# schematic-both.net
KiCad netlist of a schematic drawn in EAGLE
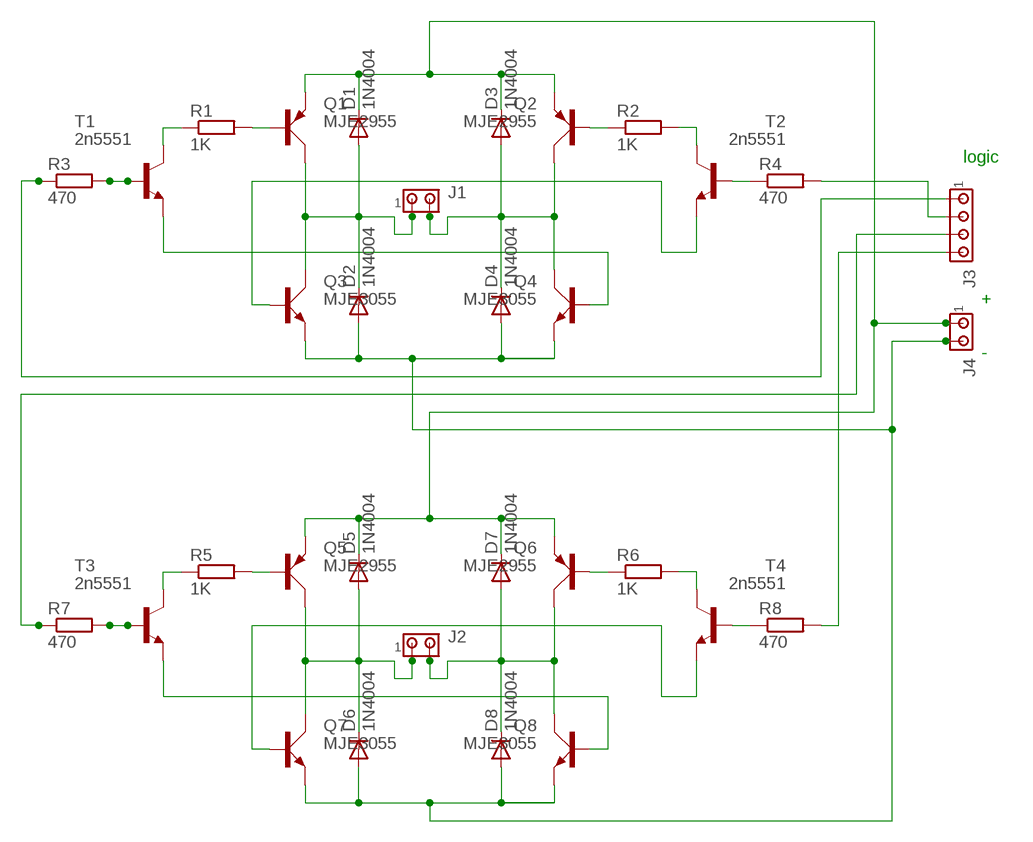
[diagram p0: schematic, sheet 1]

(export (version "E")
  (design (tool "Eeschema 10.0.6"))
  (components
    (comp (ref "D1")
      (value "1N4004")
      (footprint "eagle-import:DO41-10")
      (libsource (lib "eagle-import") (part "1N4004"))
    )
    (comp (ref "D2")
      (value "1N4004")
      (footprint "eagle-import:DO41-10")
      (libsource (lib "eagle-import") (part "1N4004"))
    )
    (comp (ref "D3")
      (value "1N4004")
      (footprint "eagle-import:DO41-10")
      (libsource (lib "eagle-import") (part "1N4004"))
    )
    (comp (ref "D4")
      (value "1N4004")
      (footprint "eagle-import:DO41-10")
      (libsource (lib "eagle-import") (part "1N4004"))
    )
    (comp (ref "D5")
      (value "1N4004")
      (footprint "eagle-import:DO41-10")
      (libsource (lib "eagle-import") (part "1N4004"))
    )
    (comp (ref "D6")
      (value "1N4004")
      (footprint "eagle-import:DO41-10")
      (libsource (lib "eagle-import") (part "1N4004"))
    )
    (comp (ref "D7")
      (value "1N4004")
      (footprint "eagle-import:DO41-10")
      (libsource (lib "eagle-import") (part "1N4004"))
    )
    (comp (ref "D8")
      (value "1N4004")
      (footprint "eagle-import:DO41-10")
      (libsource (lib "eagle-import") (part "1N4004"))
    )
    (comp (ref "J1")
      (value "MTA02-156")
      (footprint "eagle-import:1X2MTA")
      (libsource (lib "eagle-import") (part "MTA02-156"))
    )
    (comp (ref "J2")
      (value "MTA02-156")
      (footprint "eagle-import:1X2MTA")
      (libsource (lib "eagle-import") (part "MTA02-156"))
    )
    (comp (ref "J3")
      (value "MTA04-100")
      (footprint "eagle-import:10X04MTA")
      (libsource (lib "eagle-import") (part "MTA04-100"))
    )
    (comp (ref "J4")
      (value "MTA02-156")
      (footprint "eagle-import:1X2MTA")
      (libsource (lib "eagle-import") (part "MTA02-156"))
    )
    (comp (ref "Q1")
      (value "MJE2955")
      (footprint "eagle-import:TO220AV")
      (libsource (lib "eagle-import") (part "MJE2955"))
    )
    (comp (ref "Q2")
      (value "MJE2955")
      (footprint "eagle-import:TO220AV")
      (libsource (lib "eagle-import") (part "MJE2955"))
    )
    (comp (ref "Q3")
      (value "MJE3055")
      (footprint "eagle-import:TO220AV")
      (libsource (lib "eagle-import") (part "MJE3055"))
    )
    (comp (ref "Q4")
      (value "MJE3055")
      (footprint "eagle-import:TO220AV")
      (libsource (lib "eagle-import") (part "MJE3055"))
    )
    (comp (ref "Q5")
      (value "MJE2955")
      (footprint "eagle-import:TO220AV")
      (libsource (lib "eagle-import") (part "MJE2955"))
    )
    (comp (ref "Q6")
      (value "MJE2955")
      (footprint "eagle-import:TO220AV")
      (libsource (lib "eagle-import") (part "MJE2955"))
    )
    (comp (ref "Q7")
      (value "MJE3055")
      (footprint "eagle-import:TO220AV")
      (libsource (lib "eagle-import") (part "MJE3055"))
    )
    (comp (ref "Q8")
      (value "MJE3055")
      (footprint "eagle-import:TO220AV")
      (libsource (lib "eagle-import") (part "MJE3055"))
    )
    (comp (ref "R1")
      (value "1K")
      (footprint "eagle-import:0204_7")
      (libsource (lib "eagle-import") (part "R-EU_0204/7"))
    )
    (comp (ref "R2")
      (value "1K")
      (footprint "eagle-import:0204_7")
      (libsource (lib "eagle-import") (part "R-EU_0204/7"))
    )
    (comp (ref "R3")
      (value "470")
      (footprint "eagle-import:0204_7")
      (libsource (lib "eagle-import") (part "R-EU_0204/7"))
    )
    (comp (ref "R4")
      (value "470")
      (footprint "eagle-import:0204_7")
      (libsource (lib "eagle-import") (part "R-EU_0204/7"))
    )
    (comp (ref "R5")
      (value "1K")
      (footprint "eagle-import:0204_7")
      (libsource (lib "eagle-import") (part "R-EU_0204/7"))
    )
    (comp (ref "R6")
      (value "1K")
      (footprint "eagle-import:0204_7")
      (libsource (lib "eagle-import") (part "R-EU_0204/7"))
    )
    (comp (ref "R7")
      (value "470")
      (footprint "eagle-import:0204_7")
      (libsource (lib "eagle-import") (part "R-EU_0204/7"))
    )
    (comp (ref "R8")
      (value "470")
      (footprint "eagle-import:0204_7")
      (libsource (lib "eagle-import") (part "R-EU_0204/7"))
    )
    (comp (ref "T1")
      (value "2n5551")
      (footprint "eagle-import:TO92-EBC")
      (libsource (lib "eagle-import") (part "-NPN-TO92-EBC2N5551"))
    )
    (comp (ref "T2")
      (value "2n5551")
      (footprint "eagle-import:TO92-EBC")
      (libsource (lib "eagle-import") (part "-NPN-TO92-EBC2N5551"))
    )
    (comp (ref "T3")
      (value "2n5551")
      (footprint "eagle-import:TO92-EBC")
      (libsource (lib "eagle-import") (part "-NPN-TO92-EBC2N5551"))
    )
    (comp (ref "T4")
      (value "2n5551")
      (footprint "eagle-import:TO92-EBC")
      (libsource (lib "eagle-import") (part "-NPN-TO92-EBC2N5551"))
    )
  )
  (nets
    (net (code "1") (name "Net-(D1-PadA)") (class "Default")
      (node (ref "D1") (pin "A") (pinfunction "A_A") (pintype "passive"))
      (node (ref "D2") (pin "C") (pinfunction "C_C") (pintype "passive"))
      (node (ref "J1") (pin "1") (pinfunction "1_1") (pintype "passive"))
      (node (ref "Q1") (pin "C") (pinfunction "C_C") (pintype "passive"))
      (node (ref "Q3") (pin "C") (pinfunction "C_C") (pintype "passive"))
    )
    (net (code "2") (name "Net-(D1-PadC)") (class "Default")
      (node (ref "D1") (pin "C") (pinfunction "C_C") (pintype "passive"))
      (node (ref "D3") (pin "C") (pinfunction "C_C") (pintype "passive"))
      (node (ref "D5") (pin "C") (pinfunction "C_C") (pintype "passive"))
      (node (ref "D7") (pin "C") (pinfunction "C_C") (pintype "passive"))
      (node (ref "J4") (pin "1") (pinfunction "1_1") (pintype "passive"))
      (node (ref "Q1") (pin "E") (pinfunction "E_E") (pintype "passive"))
      (node (ref "Q2") (pin "E") (pinfunction "E_E") (pintype "passive"))
      (node (ref "Q5") (pin "E") (pinfunction "E_E") (pintype "passive"))
      (node (ref "Q6") (pin "E") (pinfunction "E_E") (pintype "passive"))
    )
    (net (code "3") (name "Net-(D2-PadA)") (class "Default")
      (node (ref "D2") (pin "A") (pinfunction "A_A") (pintype "passive"))
      (node (ref "D4") (pin "A") (pinfunction "A_A") (pintype "passive"))
      (node (ref "D6") (pin "A") (pinfunction "A_A") (pintype "passive"))
      (node (ref "D8") (pin "A") (pinfunction "A_A") (pintype "passive"))
      (node (ref "J4") (pin "2") (pinfunction "2_2") (pintype "passive"))
      (node (ref "Q3") (pin "E") (pinfunction "E_E") (pintype "passive"))
      (node (ref "Q4") (pin "E") (pinfunction "E_E") (pintype "passive"))
      (node (ref "Q7") (pin "E") (pinfunction "E_E") (pintype "passive"))
      (node (ref "Q8") (pin "E") (pinfunction "E_E") (pintype "passive"))
    )
    (net (code "4") (name "Net-(D3-PadA)") (class "Default")
      (node (ref "D3") (pin "A") (pinfunction "A_A") (pintype "passive"))
      (node (ref "D4") (pin "C") (pinfunction "C_C") (pintype "passive"))
      (node (ref "J1") (pin "2") (pinfunction "2_2") (pintype "passive"))
      (node (ref "Q2") (pin "C") (pinfunction "C_C") (pintype "passive"))
      (node (ref "Q4") (pin "C") (pinfunction "C_C") (pintype "passive"))
    )
    (net (code "5") (name "Net-(D5-PadA)") (class "Default")
      (node (ref "D5") (pin "A") (pinfunction "A_A") (pintype "passive"))
      (node (ref "D6") (pin "C") (pinfunction "C_C") (pintype "passive"))
      (node (ref "J2") (pin "1") (pinfunction "1_1") (pintype "passive"))
      (node (ref "Q5") (pin "C") (pinfunction "C_C") (pintype "passive"))
      (node (ref "Q7") (pin "C") (pinfunction "C_C") (pintype "passive"))
    )
    (net (code "6") (name "Net-(D7-PadA)") (class "Default")
      (node (ref "D7") (pin "A") (pinfunction "A_A") (pintype "passive"))
      (node (ref "D8") (pin "C") (pinfunction "C_C") (pintype "passive"))
      (node (ref "J2") (pin "2") (pinfunction "2_2") (pintype "passive"))
      (node (ref "Q6") (pin "C") (pinfunction "C_C") (pintype "passive"))
      (node (ref "Q8") (pin "C") (pinfunction "C_C") (pintype "passive"))
    )
    (net (code "7") (name "Net-(J3-Pad1)") (class "Default")
      (node (ref "J3") (pin "1") (pinfunction "1_1") (pintype "passive"))
      (node (ref "R3") (pin "1") (pinfunction "1_1") (pintype "passive"))
    )
    (net (code "8") (name "Net-(J3-Pad2)") (class "Default")
      (node (ref "J3") (pin "2") (pinfunction "2_2") (pintype "passive"))
      (node (ref "R4") (pin "2") (pinfunction "2_2") (pintype "passive"))
    )
    (net (code "9") (name "Net-(J3-Pad3)") (class "Default")
      (node (ref "J3") (pin "3") (pinfunction "3_3") (pintype "passive"))
      (node (ref "R7") (pin "1") (pinfunction "1_1") (pintype "passive"))
    )
    (net (code "10") (name "Net-(J3-Pad4)") (class "Default")
      (node (ref "J3") (pin "4") (pinfunction "4_4") (pintype "passive"))
      (node (ref "R8") (pin "2") (pinfunction "2_2") (pintype "passive"))
    )
    (net (code "11") (name "Net-(Q1-PadB)") (class "Default")
      (node (ref "Q1") (pin "B") (pinfunction "B_B") (pintype "passive"))
      (node (ref "R1") (pin "2") (pinfunction "2_2") (pintype "passive"))
    )
    (net (code "12") (name "Net-(Q2-PadB)") (class "Default")
      (node (ref "Q2") (pin "B") (pinfunction "B_B") (pintype "passive"))
      (node (ref "R2") (pin "1") (pinfunction "1_1") (pintype "passive"))
    )
    (net (code "13") (name "Net-(Q3-PadB)") (class "Default")
      (node (ref "Q3") (pin "B") (pinfunction "B_B") (pintype "passive"))
      (node (ref "T2") (pin "E") (pinfunction "E_E") (pintype "passive"))
    )
    (net (code "14") (name "Net-(Q4-PadB)") (class "Default")
      (node (ref "Q4") (pin "B") (pinfunction "B_B") (pintype "passive"))
      (node (ref "T1") (pin "E") (pinfunction "E_E") (pintype "passive"))
    )
    (net (code "15") (name "Net-(Q5-PadB)") (class "Default")
      (node (ref "Q5") (pin "B") (pinfunction "B_B") (pintype "passive"))
      (node (ref "R5") (pin "2") (pinfunction "2_2") (pintype "passive"))
    )
    (net (code "16") (name "Net-(Q6-PadB)") (class "Default")
      (node (ref "Q6") (pin "B") (pinfunction "B_B") (pintype "passive"))
      (node (ref "R6") (pin "1") (pinfunction "1_1") (pintype "passive"))
    )
    (net (code "17") (name "Net-(Q7-PadB)") (class "Default")
      (node (ref "Q7") (pin "B") (pinfunction "B_B") (pintype "passive"))
      (node (ref "T4") (pin "E") (pinfunction "E_E") (pintype "passive"))
    )
    (net (code "18") (name "Net-(Q8-PadB)") (class "Default")
      (node (ref "Q8") (pin "B") (pinfunction "B_B") (pintype "passive"))
      (node (ref "T3") (pin "E") (pinfunction "E_E") (pintype "passive"))
    )
    (net (code "19") (name "Net-(R1-Pad1)") (class "Default")
      (node (ref "R1") (pin "1") (pinfunction "1_1") (pintype "passive"))
      (node (ref "T1") (pin "C") (pinfunction "C_C") (pintype "passive"))
    )
    (net (code "20") (name "Net-(R2-Pad2)") (class "Default")
      (node (ref "R2") (pin "2") (pinfunction "2_2") (pintype "passive"))
      (node (ref "T2") (pin "C") (pinfunction "C_C") (pintype "passive"))
    )
    (net (code "21") (name "Net-(R3-Pad2)") (class "Default")
      (node (ref "R3") (pin "2") (pinfunction "2_2") (pintype "passive"))
      (node (ref "T1") (pin "B") (pinfunction "B_B") (pintype "passive"))
    )
    (net (code "22") (name "Net-(R4-Pad1)") (class "Default")
      (node (ref "R4") (pin "1") (pinfunction "1_1") (pintype "passive"))
      (node (ref "T2") (pin "B") (pinfunction "B_B") (pintype "passive"))
    )
    (net (code "23") (name "Net-(R5-Pad1)") (class "Default")
      (node (ref "R5") (pin "1") (pinfunction "1_1") (pintype "passive"))
      (node (ref "T3") (pin "C") (pinfunction "C_C") (pintype "passive"))
    )
    (net (code "24") (name "Net-(R6-Pad2)") (class "Default")
      (node (ref "R6") (pin "2") (pinfunction "2_2") (pintype "passive"))
      (node (ref "T4") (pin "C") (pinfunction "C_C") (pintype "passive"))
    )
    (net (code "25") (name "Net-(R7-Pad2)") (class "Default")
      (node (ref "R7") (pin "2") (pinfunction "2_2") (pintype "passive"))
      (node (ref "T3") (pin "B") (pinfunction "B_B") (pintype "passive"))
    )
    (net (code "26") (name "Net-(R8-Pad1)") (class "Default")
      (node (ref "R8") (pin "1") (pinfunction "1_1") (pintype "passive"))
      (node (ref "T4") (pin "B") (pinfunction "B_B") (pintype "passive"))
    )
  )
)
